# Sensors.net
KiCad netlist of a schematic drawn in Altium Designer
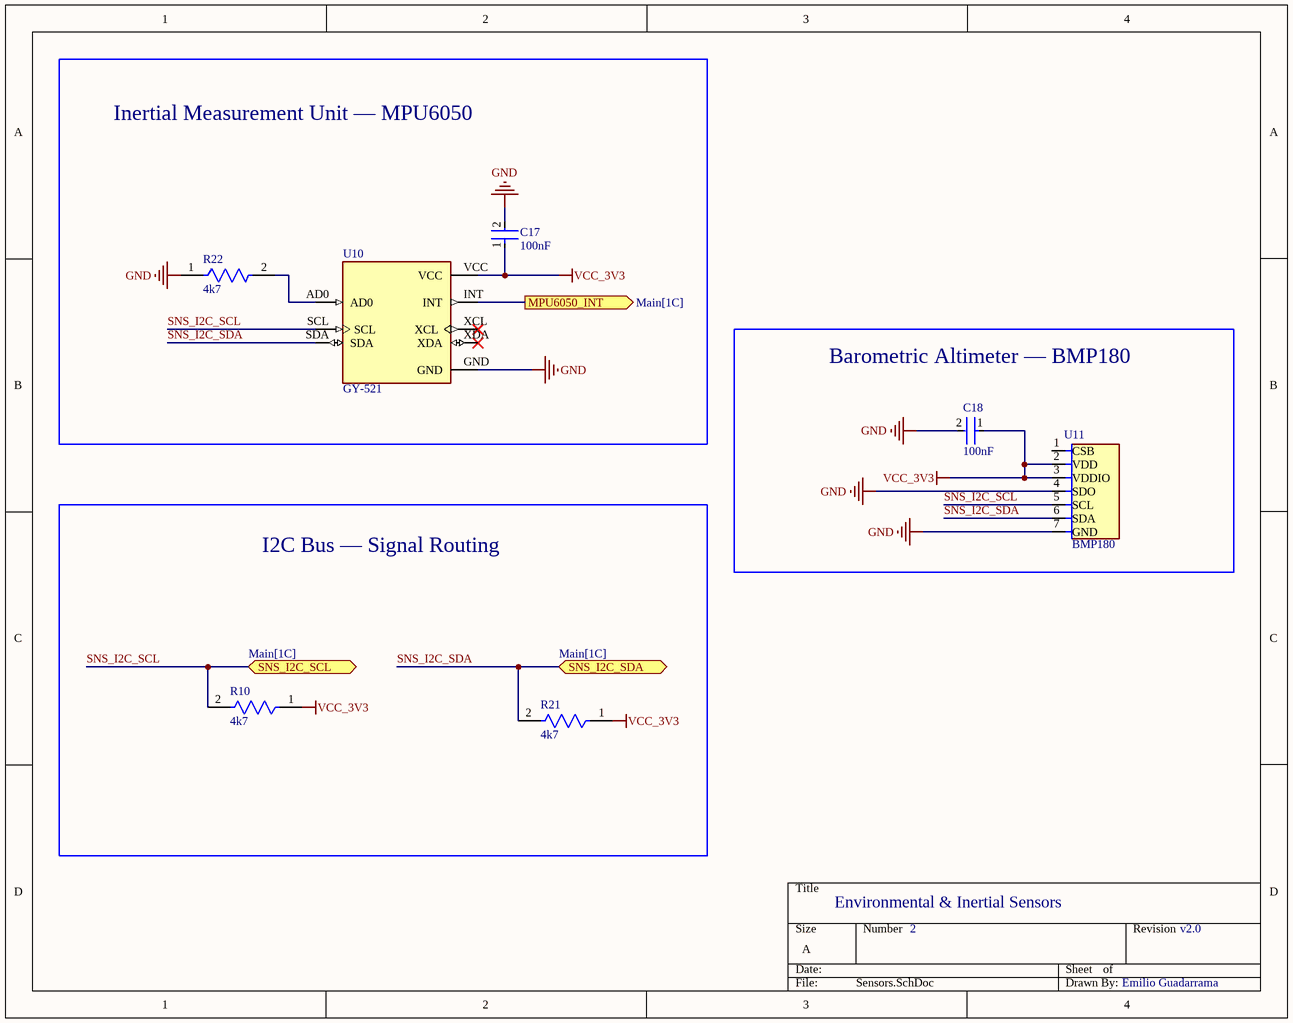
[diagram p0: Sensors.SchDoc]

(export (version "E")
  (design (tool "Eeschema 10.0.6"))
  (components
    (comp (ref "C17")
      (value "100nF")
      (footprint "FP-C0805C-DN-MFG")
      (description "CAP CER 0.1UF 50V X7R 0805")
      (fields
        (field (name "MANUFACTURER PART NUMBER") "C0805C104K5RACTU")
        (field (name "MANUFACTURER") "KEMET")
      )
      (libsource (lib "Altium Content Vault") (part "b4654b650e69147ec39a6b967a45e02"))
    )
    (comp (ref "C18")
      (value "100nF")
      (footprint "FP-C0805C-DN-MFG")
      (description "CAP CER 0.1UF 50V X7R 0805")
      (fields
        (field (name "MANUFACTURER PART NUMBER") "C0805C104K5RACTU")
        (field (name "MANUFACTURER") "KEMET")
      )
      (libsource (lib "Altium Content Vault") (part "b4654b650e69147ec39a6b967a45e02"))
    )
    (comp (ref "R10")
      (value "4k7")
      (footprint "FP-MCT0603-IPC_A")
      (description "RES SMD 100 OHM 1% 1/8W 0603")
      (fields (field (name "TOLERANCE") "0.1%"))
      (libsource (lib "Altium Content Vault") (part "1029c3af85768c4190bb7ad29bc67b5"))
    )
    (comp (ref "R21")
      (value "4k7")
      (footprint "FP-MCT0603-IPC_A")
      (description "RES SMD 100 OHM 1% 1/8W 0603")
      (fields (field (name "TOLERANCE") "0.1%"))
      (libsource (lib "Altium Content Vault") (part "1029c3af85768c4190bb7ad29bc67b5"))
    )
    (comp (ref "R22")
      (value "4k7")
      (footprint "FP-MCT0603-IPC_A")
      (description "RES SMD 100 OHM 1% 1/8W 0603")
      (fields (field (name "TOLERANCE") "0.1%"))
      (libsource (lib "Altium Content Vault") (part "1029c3af85768c4190bb7ad29bc67b5"))
    )
    (comp (ref "U10")
      (value "GY-521")
      (footprint "MODULE_GY-521")
      (description "Triple Axis Accelerometer Gyro Breakout")
      (fields (field (name "MF") "GODREAM FORDREAM CO., LIMITED"))
      (libsource (lib "GY-521_IMU_with_MountingHoles") (part "GY-521"))
    )
    (comp (ref "U11")
      (value "BMP180")
      (footprint "LGA7-1.5-3.8X3.6MM")
      (description "Pressure Sensor 4.35PSI ~ 15.95PSI (30kPa ~ 110kPa) Absolute - 16 ~ 19 b 7-VLGA")
      (fields (field (name "MF") "Bosch"))
      (libsource (lib "BMP180") (part "PRESSURE-BMP180(LGA7)"))
    )
  )
  (nets
    (net (code "1") (name "/MPU6050_INT") (class "Default")
      (node (ref "U10") (pin "INT") (pinfunction "INT_INT") (pintype "output"))
    )
    (net (code "2") (name "/SNS_I2C_SCL") (class "Default")
      (node (ref "R10") (pin "2") (pinfunction "2_2") (pintype "passive"))
      (node (ref "U10") (pin "SCL") (pinfunction "SCL_SCL") (pintype "input"))
      (node (ref "U11") (pin "5") (pinfunction "SCL_5") (pintype "bidirectional"))
    )
    (net (code "3") (name "/SNS_I2C_SDA") (class "Default")
      (node (ref "R21") (pin "2") (pinfunction "2_2") (pintype "passive"))
      (node (ref "U10") (pin "SDA") (pinfunction "SDA_SDA") (pintype "bidirectional"))
      (node (ref "U11") (pin "6") (pinfunction "SDA_6") (pintype "bidirectional"))
    )
    (net (code "4") (name "GND") (class "Default")
      (node (ref "C17") (pin "2") (pinfunction "2_2") (pintype "passive"))
      (node (ref "C18") (pin "2") (pinfunction "2_2") (pintype "passive"))
      (node (ref "R22") (pin "1") (pinfunction "1_1") (pintype "passive"))
      (node (ref "U10") (pin "GND") (pinfunction "GND_GND") (pintype "power_in"))
      (node (ref "U11") (pin "4") (pinfunction "SDO_4") (pintype "bidirectional"))
      (node (ref "U11") (pin "7") (pinfunction "GND_7") (pintype "bidirectional"))
    )
    (net (code "5") (name "Net-(R22-Pad2)") (class "Default")
      (node (ref "R22") (pin "2") (pinfunction "2_2") (pintype "passive"))
      (node (ref "U10") (pin "AD0") (pinfunction "AD0_AD0") (pintype "input"))
    )
    (net (code "6") (name "VCC_3V3") (class "Default")
      (node (ref "C17") (pin "1") (pinfunction "1_1") (pintype "passive"))
      (node (ref "C18") (pin "1") (pinfunction "1_1") (pintype "passive"))
      (node (ref "R10") (pin "1") (pinfunction "1_1") (pintype "passive"))
      (node (ref "R21") (pin "1") (pinfunction "1_1") (pintype "passive"))
      (node (ref "U10") (pin "VCC") (pinfunction "VCC_VCC") (pintype "power_in"))
      (node (ref "U11") (pin "2") (pinfunction "VDD_2") (pintype "bidirectional"))
      (node (ref "U11") (pin "3") (pinfunction "VDDIO_3") (pintype "bidirectional"))
    )
    (net (code "7") (name "unconnected-(U10-PadXCL)") (class "Default")
      (node (ref "U10") (pin "XCL") (pinfunction "XCL_XCL") (pintype "output+no_connect"))
    )
    (net (code "8") (name "unconnected-(U10-PadXDA)") (class "Default")
      (node (ref "U10") (pin "XDA") (pinfunction "XDA_XDA") (pintype "bidirectional+no_connect"))
    )
    (net (code "9") (name "unconnected-(U11-CSB-Pad1)") (class "Default")
      (node (ref "U11") (pin "1") (pinfunction "CSB_1") (pintype "bidirectional"))
    )
  )
)
